# design.net
KiCad netlist of a schematic drawn in Altium Designer
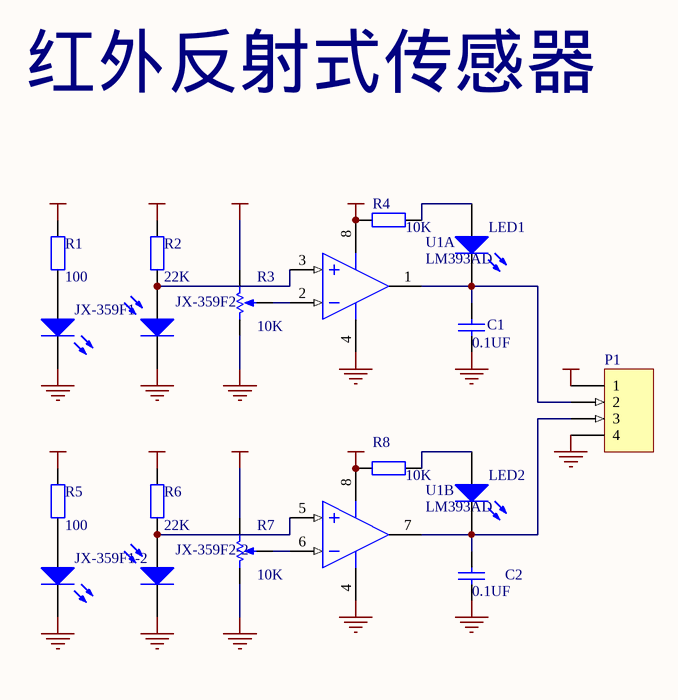
[diagram p0: 双红外反射传感器.SchDoc]

(export (version "E")
  (design (tool "Eeschema 10.0.6"))
  (components
    (comp (ref "C1")
      (value "0.1UF")
      (footprint "C1608-0603")
      (description "Capacitor (Semiconductor SIM Model)")
      (fields (field (name "PUBLISHER") "Altium Limited"))
      (libsource (lib "Miscellaneous Devices") (part "Cap Semi"))
    )
    (comp (ref "C2")
      (value "0.1UF")
      (footprint "C1608-0603")
      (description "Capacitor (Semiconductor SIM Model)")
      (fields (field (name "PUBLISHER") "Altium Limited"))
      (libsource (lib "Miscellaneous Devices") (part "Cap Semi"))
    )
    (comp (ref "JX-359F1")
      (value "~")
      (footprint "HDR1X2")
      (description "Typical BLUE SiC LED")
      (fields (field (name "PUBLISHER") "Altium Limited"))
      (libsource (lib "Miscellaneous Devices") (part "LED3"))
    )
    (comp (ref "JX-359F1-2")
      (value "~")
      (footprint "HDR1X2")
      (description "Typical BLUE SiC LED")
      (fields (field (name "PUBLISHER") "Altium Limited"))
      (libsource (lib "Miscellaneous Devices") (part "LED3"))
    )
    (comp (ref "JX-359F2")
      (value "~")
      (footprint "HDR1X2")
      (description "Photosensitive Diode")
      (fields (field (name "PUBLISHER") "Altium Limited"))
      (libsource (lib "Miscellaneous Devices") (part "Photo Sen"))
    )
    (comp (ref "JX-359F2-2")
      (value "~")
      (footprint "HDR1X2")
      (description "Photosensitive Diode")
      (fields (field (name "PUBLISHER") "Altium Limited"))
      (libsource (lib "Miscellaneous Devices") (part "Photo Sen"))
    )
    (comp (ref "LED1")
      (value "~")
      (footprint "HDR1X2")
      (description "Typical BLUE SiC LED")
      (fields (field (name "PUBLISHER") "Altium Limited"))
      (libsource (lib "Miscellaneous Devices") (part "LED3"))
    )
    (comp (ref "LED2")
      (value "~")
      (footprint "HDR1X2")
      (description "Typical BLUE SiC LED")
      (fields (field (name "PUBLISHER") "Altium Limited"))
      (libsource (lib "Miscellaneous Devices") (part "LED3"))
    )
    (comp (ref "P1")
      (value "~")
      (footprint "HDR1X4")
      (description "Header, 4-Pin")
      (fields (field (name "PUBLISHER") "Altium Limited"))
      (libsource (lib "Miscellaneous Connectors") (part "Header 4"))
    )
    (comp (ref "R1")
      (value "100")
      (footprint "C1608-0603")
      (description "Resistor")
      (fields (field (name "PUBLISHER") "Altium Limited"))
      (libsource (lib "Miscellaneous Devices") (part "Res2"))
    )
    (comp (ref "R2")
      (value "22K")
      (footprint "C1608-0603")
      (description "Resistor")
      (fields (field (name "PUBLISHER") "Altium Limited"))
      (libsource (lib "Miscellaneous Devices") (part "Res2"))
    )
    (comp (ref "R3")
      (value "10K")
      (footprint "HDR1X3")
      (description "Potentiometer")
      (fields (field (name "PUBLISHER") "Altium Limited"))
      (libsource (lib "Miscellaneous Devices") (part "RPot"))
    )
    (comp (ref "R4")
      (value "10K")
      (footprint "C1608-0603")
      (description "Resistor")
      (fields (field (name "PUBLISHER") "Altium Limited"))
      (libsource (lib "") (part "Res2_1"))
    )
    (comp (ref "R5")
      (value "100")
      (footprint "C1608-0603")
      (description "Resistor")
      (fields (field (name "PUBLISHER") "Altium Limited"))
      (libsource (lib "Miscellaneous Devices") (part "Res2"))
    )
    (comp (ref "R6")
      (value "22K")
      (footprint "C1608-0603")
      (description "Resistor")
      (fields (field (name "PUBLISHER") "Altium Limited"))
      (libsource (lib "Miscellaneous Devices") (part "Res2"))
    )
    (comp (ref "R7")
      (value "10K")
      (footprint "HDR1X3")
      (description "Potentiometer")
      (fields (field (name "PUBLISHER") "Altium Limited"))
      (libsource (lib "Miscellaneous Devices") (part "RPot"))
    )
    (comp (ref "R8")
      (value "10K")
      (footprint "C1608-0603")
      (description "Resistor")
      (fields (field (name "PUBLISHER") "Altium Limited"))
      (libsource (lib "") (part "Res2_1"))
    )
    (comp (ref "U1")
      (value "LM393AD")
      (footprint "SO8")
      (description "Low-Power Dual Voltage Comparator")
      (fields (field (name "PUBLISHER") "Altium Limited"))
      (libsource (lib "ST Analog Comparator") (part "LM393AD"))
    )
  )
  (nets
    (net (code "1") (name "GND") (class "Default")
      (node (ref "C1") (pin "1") (pinfunction "1_1") (pintype "passive"))
      (node (ref "C2") (pin "1") (pinfunction "1_1") (pintype "passive"))
      (node (ref "JX-359F1") (pin "2") (pinfunction "K_2") (pintype "passive"))
      (node (ref "JX-359F1-2") (pin "2") (pinfunction "K_2") (pintype "passive"))
      (node (ref "JX-359F2") (pin "2") (pinfunction "K_2") (pintype "passive"))
      (node (ref "JX-359F2-2") (pin "2") (pinfunction "K_2") (pintype "passive"))
      (node (ref "P1") (pin "4") (pinfunction "4_4") (pintype "power_in"))
      (node (ref "R3") (pin "2") (pinfunction "BOT_2") (pintype "passive"))
      (node (ref "R7") (pin "2") (pinfunction "BOT_2") (pintype "passive"))
      (node (ref "U1") (pin "4") (pinfunction "V+_4") (pintype "power_in"))
    )
    (net (code "2") (name "Net-(JX-359F1-2-A)") (class "Default")
      (node (ref "JX-359F1-2") (pin "1") (pinfunction "A_1") (pintype "passive"))
      (node (ref "R5") (pin "1") (pinfunction "1_1") (pintype "passive"))
    )
    (net (code "3") (name "Net-(JX-359F1-A)") (class "Default")
      (node (ref "JX-359F1") (pin "1") (pinfunction "A_1") (pintype "passive"))
      (node (ref "R1") (pin "1") (pinfunction "1_1") (pintype "passive"))
    )
    (net (code "4") (name "Net-(JX-359F2-2-A)") (class "Default")
      (node (ref "JX-359F2-2") (pin "1") (pinfunction "A_1") (pintype "passive"))
      (node (ref "R6") (pin "1") (pinfunction "1_1") (pintype "passive"))
      (node (ref "U1") (pin "5") (pinfunction "IN+_5") (pintype "input"))
    )
    (net (code "5") (name "Net-(JX-359F2-A)") (class "Default")
      (node (ref "JX-359F2") (pin "1") (pinfunction "A_1") (pintype "passive"))
      (node (ref "R2") (pin "1") (pinfunction "1_1") (pintype "passive"))
      (node (ref "U1") (pin "3") (pinfunction "IN+_3") (pintype "input"))
    )
    (net (code "6") (name "Net-(LED1-A)") (class "Default")
      (node (ref "LED1") (pin "1") (pinfunction "A_1") (pintype "passive"))
      (node (ref "R4") (pin "1") (pinfunction "1_1") (pintype "passive"))
    )
    (net (code "7") (name "Net-(LED1-K)") (class "Default")
      (node (ref "C1") (pin "2") (pinfunction "2_2") (pintype "passive"))
      (node (ref "LED1") (pin "2") (pinfunction "K_2") (pintype "passive"))
      (node (ref "P1") (pin "2") (pinfunction "2_2") (pintype "input"))
      (node (ref "U1") (pin "1") (pinfunction "OUT_1") (pintype "open_collector"))
    )
    (net (code "8") (name "Net-(LED2-A)") (class "Default")
      (node (ref "LED2") (pin "1") (pinfunction "A_1") (pintype "passive"))
      (node (ref "R8") (pin "1") (pinfunction "1_1") (pintype "passive"))
    )
    (net (code "9") (name "Net-(LED2-K)") (class "Default")
      (node (ref "C2") (pin "2") (pinfunction "2_2") (pintype "passive"))
      (node (ref "LED2") (pin "2") (pinfunction "K_2") (pintype "passive"))
      (node (ref "P1") (pin "3") (pinfunction "3_3") (pintype "input"))
      (node (ref "U1") (pin "7") (pinfunction "OUT_7") (pintype "open_collector"))
    )
    (net (code "10") (name "Net-(R3-TAP)") (class "Default")
      (node (ref "R3") (pin "3") (pinfunction "TAP_3") (pintype "passive"))
      (node (ref "U1") (pin "2") (pinfunction "IN-_2") (pintype "input"))
    )
    (net (code "11") (name "Net-(R7-TAP)") (class "Default")
      (node (ref "R7") (pin "3") (pinfunction "TAP_3") (pintype "passive"))
      (node (ref "U1") (pin "6") (pinfunction "IN-_6") (pintype "input"))
    )
    (net (code "12") (name "VCC") (class "Default")
      (node (ref "P1") (pin "1") (pinfunction "1_1") (pintype "power_in"))
      (node (ref "R1") (pin "2") (pinfunction "2_2") (pintype "passive"))
      (node (ref "R2") (pin "2") (pinfunction "2_2") (pintype "passive"))
      (node (ref "R3") (pin "1") (pinfunction "TOP_1") (pintype "passive"))
      (node (ref "R4") (pin "2") (pinfunction "2_2") (pintype "passive"))
      (node (ref "R5") (pin "2") (pinfunction "2_2") (pintype "passive"))
      (node (ref "R6") (pin "2") (pinfunction "2_2") (pintype "passive"))
      (node (ref "R7") (pin "1") (pinfunction "TOP_1") (pintype "passive"))
      (node (ref "R8") (pin "2") (pinfunction "2_2") (pintype "passive"))
      (node (ref "U1") (pin "8") (pinfunction "V-_8") (pintype "power_in"))
    )
  )
)
